# RL78G10_E1.net
KiCad netlist of a schematic drawn in EAGLE
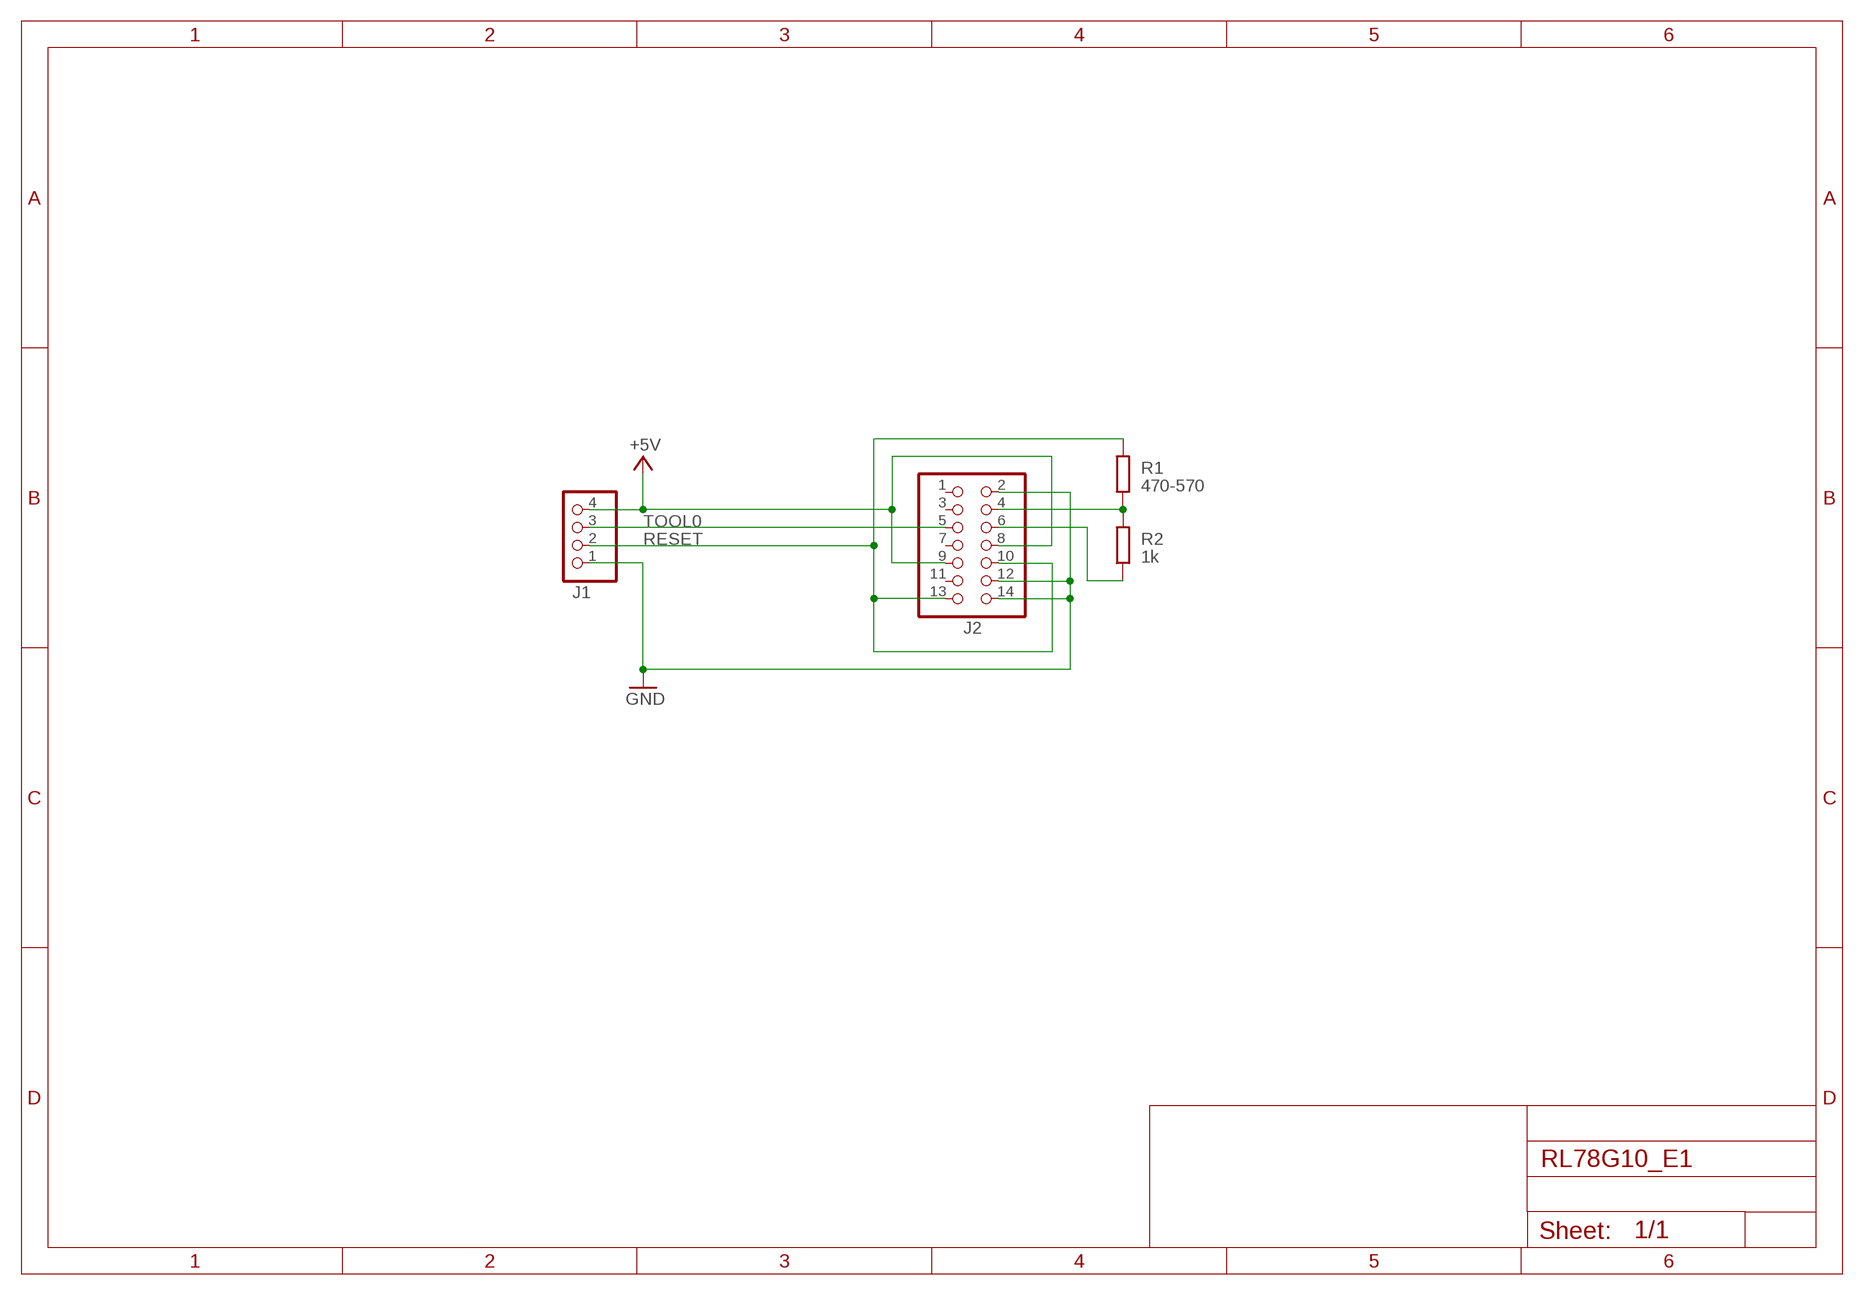
[diagram p0: schematic, sheet 1]

(export (version "E")
  (design (tool "Eeschema 10.0.6"))
  (components
    (comp (ref "J1")
      (value "PINHD_1X4")
      (footprint "eagle-import:PINHD_1X04")
      (libsource (lib "eagle-import") (part "PINHD_1X4"))
    )
    (comp (ref "J2")
      (value "PINHD_2X07")
      (footprint "eagle-import:PINHD_2X07")
      (libsource (lib "eagle-import") (part "PINHD_2X07"))
    )
    (comp (ref "R1")
      (value "470-570")
      (footprint "eagle-import:R0603")
      (libsource (lib "eagle-import") (part "R-EU_R0603"))
    )
    (comp (ref "R2")
      (value "1k")
      (footprint "eagle-import:R0603")
      (libsource (lib "eagle-import") (part "R-EU_R0603"))
    )
  )
  (nets
    (net (code "1") (name "+5V") (class "Default")
      (node (ref "J1") (pin "4") (pinfunction "4_4") (pintype "passive"))
      (node (ref "J2") (pin "8") (pinfunction "8_8") (pintype "passive"))
      (node (ref "J2") (pin "9") (pinfunction "9_9") (pintype "passive"))
    )
    (net (code "2") (name "/RESET") (class "Default")
      (node (ref "J1") (pin "2") (pinfunction "2_2") (pintype "passive"))
      (node (ref "J2") (pin "10") (pinfunction "10_10") (pintype "passive"))
      (node (ref "J2") (pin "13") (pinfunction "13_13") (pintype "passive"))
      (node (ref "R1") (pin "2") (pinfunction "2_2") (pintype "passive"))
    )
    (net (code "3") (name "/TOOL0") (class "Default")
      (node (ref "J1") (pin "3") (pinfunction "3_3") (pintype "passive"))
      (node (ref "J2") (pin "5") (pinfunction "5_5") (pintype "passive"))
    )
    (net (code "4") (name "GND") (class "Default")
      (node (ref "J1") (pin "1") (pinfunction "1_1") (pintype "passive"))
      (node (ref "J2") (pin "12") (pinfunction "12_12") (pintype "passive"))
      (node (ref "J2") (pin "14") (pinfunction "14_14") (pintype "passive"))
      (node (ref "J2") (pin "2") (pinfunction "2_2") (pintype "passive"))
    )
    (net (code "5") (name "Net-(J2-Pad4)") (class "Default")
      (node (ref "J2") (pin "4") (pinfunction "4_4") (pintype "passive"))
      (node (ref "R1") (pin "1") (pinfunction "1_1") (pintype "passive"))
      (node (ref "R2") (pin "2") (pinfunction "2_2") (pintype "passive"))
    )
    (net (code "6") (name "Net-(J2-Pad6)") (class "Default")
      (node (ref "J2") (pin "6") (pinfunction "6_6") (pintype "passive"))
      (node (ref "R2") (pin "1") (pinfunction "1_1") (pintype "passive"))
    )
    (net (code "7") (name "unconnected-(J2-Pad1)") (class "Default")
      (node (ref "J2") (pin "1") (pinfunction "1_1") (pintype "passive"))
    )
    (net (code "8") (name "unconnected-(J2-Pad3)") (class "Default")
      (node (ref "J2") (pin "3") (pinfunction "3_3") (pintype "passive"))
    )
    (net (code "9") (name "unconnected-(J2-Pad7)") (class "Default")
      (node (ref "J2") (pin "7") (pinfunction "7_7") (pintype "passive"))
    )
    (net (code "10") (name "unconnected-(J2-Pad11)") (class "Default")
      (node (ref "J2") (pin "11") (pinfunction "11_11") (pintype "passive"))
    )
  )
)
